# 2_LVDS.net
KiCad netlist of a schematic drawn in Altium Designer
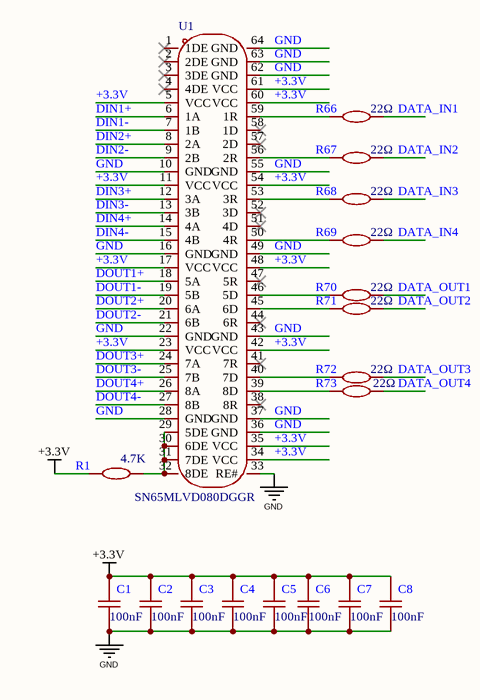
[diagram p0: 2_LVDS.schdoc]

(export (version "E")
  (design (tool "Eeschema 10.0.6"))
  (components
    (comp (ref "C1") (value "100nF") (footprint "C0603") (libsource (lib "34567890") (part "CAP_0603")))
    (comp (ref "C2") (value "100nF") (footprint "C0603") (libsource (lib "34567890") (part "CAP_0603")))
    (comp (ref "C3") (value "100nF") (footprint "C0603") (libsource (lib "34567890") (part "CAP_0603")))
    (comp (ref "C4") (value "100nF") (footprint "C0603") (libsource (lib "34567890") (part "CAP_0603")))
    (comp (ref "C5") (value "100nF") (footprint "C0603") (libsource (lib "34567890") (part "CAP_0603")))
    (comp (ref "C6") (value "100nF") (footprint "C0603") (libsource (lib "34567890") (part "CAP_0603")))
    (comp (ref "C7") (value "100nF") (footprint "C0603") (libsource (lib "34567890") (part "CAP_0603")))
    (comp (ref "C8") (value "100nF") (footprint "C0603") (libsource (lib "34567890") (part "CAP_0603")))
    (comp (ref "R1") (value "4.7K") (footprint "R0603") (libsource (lib "34567890") (part "Res_0603")))
    (comp (ref "R66") (value "22Ω") (footprint "R0603") (libsource (lib "34567890") (part "Res_0603")))
    (comp (ref "R67") (value "22Ω") (footprint "R0603") (libsource (lib "34567890") (part "Res_0603")))
    (comp (ref "R68") (value "22Ω") (footprint "R0603") (libsource (lib "34567890") (part "Res_0603")))
    (comp (ref "R69") (value "22Ω") (footprint "R0603") (libsource (lib "34567890") (part "Res_0603")))
    (comp (ref "R70") (value "22Ω") (footprint "R0603") (libsource (lib "34567890") (part "Res_0603")))
    (comp (ref "R71") (value "22Ω") (footprint "R0603") (libsource (lib "34567890") (part "Res_0603")))
    (comp (ref "R72") (value "22Ω") (footprint "R0603") (libsource (lib "34567890") (part "Res_0603")))
    (comp (ref "R73") (value "22Ω") (footprint "R0603") (libsource (lib "34567890") (part "Res_0603")))
    (comp (ref "U1")
      (value "SN65MLVD080DGGR")
      (footprint "TSSOP-64_L17.0-W6.1-P0.50-LS8.1-BL")
      (libsource (lib "34567890") (part "SN65MLVD080DGGR"))
    )
  )
  (nets
    (net (code "1") (name "+3.3V") (class "Default")
      (node (ref "C1") (pin "2") (pinfunction "2_2") (pintype "passive"))
      (node (ref "C2") (pin "2") (pinfunction "2_2") (pintype "passive"))
      (node (ref "C3") (pin "2") (pinfunction "2_2") (pintype "passive"))
      (node (ref "C4") (pin "2") (pinfunction "2_2") (pintype "passive"))
      (node (ref "C5") (pin "2") (pinfunction "2_2") (pintype "passive"))
      (node (ref "C6") (pin "2") (pinfunction "2_2") (pintype "passive"))
      (node (ref "C7") (pin "2") (pinfunction "2_2") (pintype "passive"))
      (node (ref "C8") (pin "2") (pinfunction "2_2") (pintype "passive"))
      (node (ref "R1") (pin "1") (pinfunction "1_1") (pintype "passive"))
      (node (ref "U1") (pin "11") (pinfunction "VCC_11") (pintype "passive"))
      (node (ref "U1") (pin "17") (pinfunction "VCC_17") (pintype "passive"))
      (node (ref "U1") (pin "23") (pinfunction "VCC_23") (pintype "passive"))
      (node (ref "U1") (pin "34") (pinfunction "VCC_34") (pintype "passive"))
      (node (ref "U1") (pin "35") (pinfunction "VCC_35") (pintype "passive"))
      (node (ref "U1") (pin "42") (pinfunction "VCC_42") (pintype "passive"))
      (node (ref "U1") (pin "48") (pinfunction "VCC_48") (pintype "passive"))
      (node (ref "U1") (pin "5") (pinfunction "VCC_5") (pintype "passive"))
      (node (ref "U1") (pin "54") (pinfunction "VCC_54") (pintype "passive"))
      (node (ref "U1") (pin "60") (pinfunction "VCC_60") (pintype "passive"))
      (node (ref "U1") (pin "61") (pinfunction "VCC_61") (pintype "passive"))
    )
    (net (code "2") (name "/DATA_IN1") (class "Default")
      (node (ref "R66") (pin "2") (pinfunction "2_2") (pintype "passive"))
    )
    (net (code "3") (name "/DATA_IN2") (class "Default")
      (node (ref "R67") (pin "2") (pinfunction "2_2") (pintype "passive"))
    )
    (net (code "4") (name "/DATA_IN3") (class "Default")
      (node (ref "R68") (pin "2") (pinfunction "2_2") (pintype "passive"))
    )
    (net (code "5") (name "/DATA_IN4") (class "Default")
      (node (ref "R69") (pin "2") (pinfunction "2_2") (pintype "passive"))
    )
    (net (code "6") (name "/DATA_OUT1") (class "Default")
      (node (ref "R70") (pin "2") (pinfunction "2_2") (pintype "passive"))
    )
    (net (code "7") (name "/DATA_OUT2") (class "Default")
      (node (ref "R71") (pin "2") (pinfunction "2_2") (pintype "passive"))
    )
    (net (code "8") (name "/DATA_OUT3") (class "Default")
      (node (ref "R72") (pin "2") (pinfunction "2_2") (pintype "passive"))
    )
    (net (code "9") (name "/DATA_OUT4") (class "Default")
      (node (ref "R73") (pin "2") (pinfunction "2_2") (pintype "passive"))
    )
    (net (code "10") (name "/DIN1+") (class "Default")
      (node (ref "U1") (pin "6") (pinfunction "1A_6") (pintype "passive"))
    )
    (net (code "11") (name "/DIN1-") (class "Default")
      (node (ref "U1") (pin "7") (pinfunction "1B_7") (pintype "passive"))
    )
    (net (code "12") (name "/DIN2+") (class "Default")
      (node (ref "U1") (pin "8") (pinfunction "2A_8") (pintype "passive"))
    )
    (net (code "13") (name "/DIN2-") (class "Default")
      (node (ref "U1") (pin "9") (pinfunction "2B_9") (pintype "passive"))
    )
    (net (code "14") (name "/DIN3+") (class "Default")
      (node (ref "U1") (pin "12") (pinfunction "3A_12") (pintype "passive"))
    )
    (net (code "15") (name "/DIN3-") (class "Default")
      (node (ref "U1") (pin "13") (pinfunction "3B_13") (pintype "passive"))
    )
    (net (code "16") (name "/DIN4+") (class "Default")
      (node (ref "U1") (pin "14") (pinfunction "4A_14") (pintype "passive"))
    )
    (net (code "17") (name "/DIN4-") (class "Default")
      (node (ref "U1") (pin "15") (pinfunction "4B_15") (pintype "passive"))
    )
    (net (code "18") (name "/DOUT1+") (class "Default")
      (node (ref "U1") (pin "18") (pinfunction "5A_18") (pintype "passive"))
    )
    (net (code "19") (name "/DOUT1-") (class "Default")
      (node (ref "U1") (pin "19") (pinfunction "5B_19") (pintype "passive"))
    )
    (net (code "20") (name "/DOUT2+") (class "Default")
      (node (ref "U1") (pin "20") (pinfunction "6A_20") (pintype "passive"))
    )
    (net (code "21") (name "/DOUT2-") (class "Default")
      (node (ref "U1") (pin "21") (pinfunction "6B_21") (pintype "passive"))
    )
    (net (code "22") (name "/DOUT3+") (class "Default")
      (node (ref "U1") (pin "24") (pinfunction "7A_24") (pintype "passive"))
    )
    (net (code "23") (name "/DOUT3-") (class "Default")
      (node (ref "U1") (pin "25") (pinfunction "7B_25") (pintype "passive"))
    )
    (net (code "24") (name "/DOUT4+") (class "Default")
      (node (ref "U1") (pin "26") (pinfunction "8A_26") (pintype "passive"))
    )
    (net (code "25") (name "/DOUT4-") (class "Default")
      (node (ref "U1") (pin "27") (pinfunction "8B_27") (pintype "passive"))
    )
    (net (code "26") (name "GND") (class "Default")
      (node (ref "C1") (pin "1") (pinfunction "1_1") (pintype "passive"))
      (node (ref "C2") (pin "1") (pinfunction "1_1") (pintype "passive"))
      (node (ref "C3") (pin "1") (pinfunction "1_1") (pintype "passive"))
      (node (ref "C4") (pin "1") (pinfunction "1_1") (pintype "passive"))
      (node (ref "C5") (pin "1") (pinfunction "1_1") (pintype "passive"))
      (node (ref "C6") (pin "1") (pinfunction "1_1") (pintype "passive"))
      (node (ref "C7") (pin "1") (pinfunction "1_1") (pintype "passive"))
      (node (ref "C8") (pin "1") (pinfunction "1_1") (pintype "passive"))
      (node (ref "U1") (pin "10") (pinfunction "GND_10") (pintype "passive"))
      (node (ref "U1") (pin "16") (pinfunction "GND_16") (pintype "passive"))
      (node (ref "U1") (pin "22") (pinfunction "GND_22") (pintype "passive"))
      (node (ref "U1") (pin "28") (pinfunction "GND_28") (pintype "passive"))
      (node (ref "U1") (pin "33") (pinfunction "RE#_33") (pintype "passive"))
      (node (ref "U1") (pin "36") (pinfunction "GND_36") (pintype "passive"))
      (node (ref "U1") (pin "37") (pinfunction "GND_37") (pintype "passive"))
      (node (ref "U1") (pin "43") (pinfunction "GND_43") (pintype "passive"))
      (node (ref "U1") (pin "49") (pinfunction "GND_49") (pintype "passive"))
      (node (ref "U1") (pin "55") (pinfunction "GND_55") (pintype "passive"))
      (node (ref "U1") (pin "62") (pinfunction "GND_62") (pintype "passive"))
      (node (ref "U1") (pin "63") (pinfunction "GND_63") (pintype "passive"))
      (node (ref "U1") (pin "64") (pinfunction "GND_64") (pintype "passive"))
    )
    (net (code "27") (name "Net-(U1-1R)") (class "Default")
      (node (ref "R66") (pin "1") (pinfunction "1_1") (pintype "passive"))
      (node (ref "U1") (pin "59") (pinfunction "1R_59") (pintype "passive"))
    )
    (net (code "28") (name "Net-(U1-2R)") (class "Default")
      (node (ref "R67") (pin "1") (pinfunction "1_1") (pintype "passive"))
      (node (ref "U1") (pin "56") (pinfunction "2R_56") (pintype "passive"))
    )
    (net (code "29") (name "Net-(U1-3R)") (class "Default")
      (node (ref "R68") (pin "1") (pinfunction "1_1") (pintype "passive"))
      (node (ref "U1") (pin "53") (pinfunction "3R_53") (pintype "passive"))
    )
    (net (code "30") (name "Net-(U1-4R)") (class "Default")
      (node (ref "R69") (pin "1") (pinfunction "1_1") (pintype "passive"))
      (node (ref "U1") (pin "50") (pinfunction "4R_50") (pintype "passive"))
    )
    (net (code "31") (name "Net-(U1-5D)") (class "Default")
      (node (ref "R70") (pin "1") (pinfunction "1_1") (pintype "passive"))
      (node (ref "U1") (pin "46") (pinfunction "5D_46") (pintype "passive"))
    )
    (net (code "32") (name "Net-(U1-5DE)") (class "Default")
      (node (ref "R1") (pin "2") (pinfunction "2_2") (pintype "passive"))
      (node (ref "U1") (pin "29") (pinfunction "5DE_29") (pintype "passive"))
      (node (ref "U1") (pin "30") (pinfunction "6DE_30") (pintype "passive"))
      (node (ref "U1") (pin "31") (pinfunction "7DE_31") (pintype "passive"))
      (node (ref "U1") (pin "32") (pinfunction "8DE_32") (pintype "passive"))
    )
    (net (code "33") (name "Net-(U1-6D)") (class "Default")
      (node (ref "R71") (pin "1") (pinfunction "1_1") (pintype "passive"))
      (node (ref "U1") (pin "45") (pinfunction "6D_45") (pintype "passive"))
    )
    (net (code "34") (name "Net-(U1-7D)") (class "Default")
      (node (ref "R72") (pin "1") (pinfunction "1_1") (pintype "passive"))
      (node (ref "U1") (pin "40") (pinfunction "7D_40") (pintype "passive"))
    )
    (net (code "35") (name "Net-(U1-8D)") (class "Default")
      (node (ref "R73") (pin "1") (pinfunction "1_1") (pintype "passive"))
      (node (ref "U1") (pin "39") (pinfunction "8D_39") (pintype "passive"))
    )
    (net (code "36") (name "unconnected-(U1-1D-Pad58)") (class "Default")
      (node (ref "U1") (pin "58") (pinfunction "1D_58") (pintype "passive+no_connect"))
    )
    (net (code "37") (name "unconnected-(U1-1DE-Pad1)") (class "Default")
      (node (ref "U1") (pin "1") (pinfunction "1DE_1") (pintype "passive+no_connect"))
    )
    (net (code "38") (name "unconnected-(U1-2D-Pad57)") (class "Default")
      (node (ref "U1") (pin "57") (pinfunction "2D_57") (pintype "passive+no_connect"))
    )
    (net (code "39") (name "unconnected-(U1-2DE-Pad2)") (class "Default")
      (node (ref "U1") (pin "2") (pinfunction "2DE_2") (pintype "passive+no_connect"))
    )
    (net (code "40") (name "unconnected-(U1-3D-Pad52)") (class "Default")
      (node (ref "U1") (pin "52") (pinfunction "3D_52") (pintype "passive+no_connect"))
    )
    (net (code "41") (name "unconnected-(U1-3DE-Pad3)") (class "Default")
      (node (ref "U1") (pin "3") (pinfunction "3DE_3") (pintype "passive+no_connect"))
    )
    (net (code "42") (name "unconnected-(U1-4D-Pad51)") (class "Default")
      (node (ref "U1") (pin "51") (pinfunction "4D_51") (pintype "passive+no_connect"))
    )
    (net (code "43") (name "unconnected-(U1-4DE-Pad4)") (class "Default")
      (node (ref "U1") (pin "4") (pinfunction "4DE_4") (pintype "passive+no_connect"))
    )
    (net (code "44") (name "unconnected-(U1-5R-Pad47)") (class "Default")
      (node (ref "U1") (pin "47") (pinfunction "5R_47") (pintype "passive+no_connect"))
    )
    (net (code "45") (name "unconnected-(U1-6R-Pad44)") (class "Default")
      (node (ref "U1") (pin "44") (pinfunction "6R_44") (pintype "passive+no_connect"))
    )
    (net (code "46") (name "unconnected-(U1-7R-Pad41)") (class "Default")
      (node (ref "U1") (pin "41") (pinfunction "7R_41") (pintype "passive+no_connect"))
    )
    (net (code "47") (name "unconnected-(U1-8R-Pad38)") (class "Default")
      (node (ref "U1") (pin "38") (pinfunction "8R_38") (pintype "passive+no_connect"))
    )
  )
)
